# design.net
KiCad netlist of a schematic drawn in Altium Designer
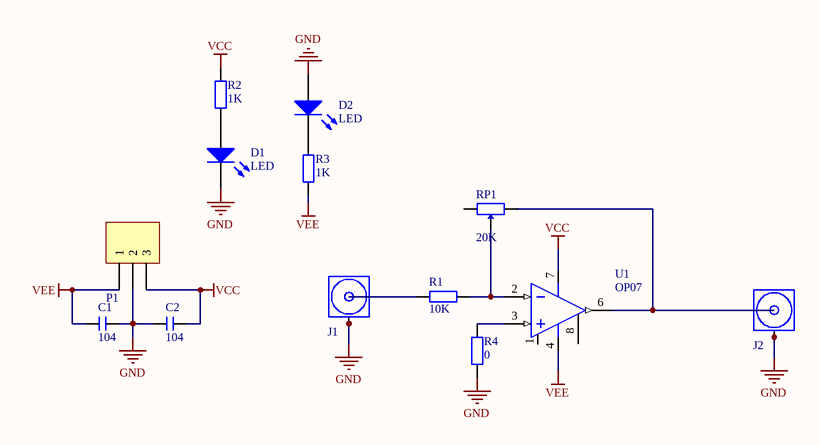
[diagram p0: 反向放大器.SchDoc]

(export (version "E")
  (design (tool "Eeschema 10.0.6"))
  (components
    (comp (ref "C1")
      (value "104")
      (footprint "C 0805")
      (description "无极性贴片电容")
      (fields (field (name "版权归属") "源创客"))
      (libsource (lib "电阻-电容-电感") (part "C"))
    )
    (comp (ref "C2")
      (value "104")
      (footprint "C 0805")
      (description "无极性贴片电容")
      (fields (field (name "版权归属") "源创客"))
      (libsource (lib "电阻-电容-电感") (part "C"))
    )
    (comp (ref "D1")
      (value "LED")
      (footprint "LED_0805")
      (description "发光二极管")
      (fields (field (name "PUBLISHER") "Altium Limited"))
      (libsource (lib "LIB") (part "LED"))
    )
    (comp (ref "D2")
      (value "LED")
      (footprint "LED_0805")
      (description "发光二极管")
      (fields (field (name "PUBLISHER") "Altium Limited"))
      (libsource (lib "LIB") (part "LED"))
    )
    (comp (ref "J1") (value "COAX") (footprint "MCX5.08-5-H") (libsource (lib "LIB") (part "COAX")))
    (comp (ref "J2") (value "COAX") (footprint "MCX5.08-5-H") (libsource (lib "LIB") (part "COAX")))
    (comp (ref "P1")
      (value "Header 3")
      (footprint "HDR3X1_B2")
      (description "接插件")
      (fields (field (name "PUBLISHER") "Altium Limited"))
      (libsource (lib "LIB") (part "Header 3"))
    )
    (comp (ref "R1")
      (value "10K")
      (footprint "R 0805")
      (description "贴片电阻")
      (fields (field (name "版权归属") "源创客"))
      (libsource (lib "电阻-电容-电感") (part "R"))
    )
    (comp (ref "R2")
      (value "1K")
      (footprint "R 0805")
      (description "贴片电阻")
      (fields (field (name "版权归属") "源创客"))
      (libsource (lib "电阻-电容-电感") (part "R"))
    )
    (comp (ref "R3")
      (value "1K")
      (footprint "R 0805")
      (description "贴片电阻")
      (fields (field (name "版权归属") "源创客"))
      (libsource (lib "电阻-电容-电感") (part "R"))
    )
    (comp (ref "R4")
      (value "0")
      (footprint "R 0603")
      (description "贴片电阻")
      (fields (field (name "版权归属") "源创客"))
      (libsource (lib "电阻-电容-电感") (part "R"))
    )
    (comp (ref "RP1")
      (value "20K")
      (footprint "3296W")
      (description "插件单联电位器")
      (fields (field (name "版权归属") "源创客"))
      (libsource (lib "电阻-电容-电感") (part "RP-ID"))
    )
    (comp (ref "U1")
      (value "OP07")
      (footprint "SO8_L")
      (description "Precision Operational Amplifiers")
      (libsource (lib "LIB") (part "OP07"))
    )
  )
  (nets
    (net (code "1") (name "GND") (class "Default")
      (node (ref "C1") (pin "2") (pinfunction "2_2") (pintype "passive"))
      (node (ref "C2") (pin "1") (pinfunction "1_1") (pintype "passive"))
      (node (ref "D1") (pin "2") (pinfunction "K_2") (pintype "passive"))
      (node (ref "D2") (pin "1") (pinfunction "A_1") (pintype "passive"))
      (node (ref "J1") (pin "2") (pinfunction "GND_2") (pintype "passive"))
      (node (ref "J1") (pin "3") (pinfunction "GND_3") (pintype "passive"))
      (node (ref "J1") (pin "4") (pinfunction "GND_4") (pintype "passive"))
      (node (ref "J1") (pin "5") (pinfunction "GND_5") (pintype "passive"))
      (node (ref "J2") (pin "2") (pinfunction "GND_2") (pintype "passive"))
      (node (ref "J2") (pin "3") (pinfunction "GND_3") (pintype "passive"))
      (node (ref "J2") (pin "4") (pinfunction "GND_4") (pintype "passive"))
      (node (ref "J2") (pin "5") (pinfunction "GND_5") (pintype "passive"))
      (node (ref "P1") (pin "2") (pinfunction "2_2") (pintype "passive"))
      (node (ref "R4") (pin "1") (pinfunction "1_1") (pintype "passive"))
    )
    (net (code "2") (name "Net-(D1-A)") (class "Default")
      (node (ref "D1") (pin "1") (pinfunction "A_1") (pintype "passive"))
      (node (ref "R2") (pin "1") (pinfunction "1_1") (pintype "passive"))
    )
    (net (code "3") (name "Net-(D2-K)") (class "Default")
      (node (ref "D2") (pin "2") (pinfunction "K_2") (pintype "passive"))
      (node (ref "R3") (pin "2") (pinfunction "2_2") (pintype "passive"))
    )
    (net (code "4") (name "Net-(J1-Signal)") (class "Default")
      (node (ref "J1") (pin "1") (pinfunction "Signal_1") (pintype "passive"))
      (node (ref "R1") (pin "1") (pinfunction "1_1") (pintype "passive"))
    )
    (net (code "5") (name "Net-(J2-Signal)") (class "Default")
      (node (ref "J2") (pin "1") (pinfunction "Signal_1") (pintype "passive"))
      (node (ref "RP1") (pin "1") (pinfunction "1_1") (pintype "passive"))
      (node (ref "U1") (pin "6") (pinfunction "OUT_6") (pintype "output"))
    )
    (net (code "6") (name "Net-(U1-IN+)") (class "Default")
      (node (ref "R4") (pin "2") (pinfunction "2_2") (pintype "passive"))
      (node (ref "U1") (pin "3") (pinfunction "IN+_3") (pintype "input"))
    )
    (net (code "7") (name "Net-(U1-IN-)") (class "Default")
      (node (ref "R1") (pin "2") (pinfunction "2_2") (pintype "passive"))
      (node (ref "RP1") (pin "2") (pinfunction "2_2") (pintype "passive"))
      (node (ref "U1") (pin "2") (pinfunction "IN-_2") (pintype "input"))
    )
    (net (code "8") (name "VCC") (class "Default")
      (node (ref "C2") (pin "2") (pinfunction "2_2") (pintype "passive"))
      (node (ref "P1") (pin "3") (pinfunction "3_3") (pintype "passive"))
      (node (ref "R2") (pin "2") (pinfunction "2_2") (pintype "passive"))
      (node (ref "U1") (pin "7") (pinfunction "V+_7") (pintype "power_in"))
    )
    (net (code "9") (name "VEE") (class "Default")
      (node (ref "C1") (pin "1") (pinfunction "1_1") (pintype "passive"))
      (node (ref "P1") (pin "1") (pinfunction "1_1") (pintype "passive"))
      (node (ref "R3") (pin "1") (pinfunction "1_1") (pintype "passive"))
      (node (ref "U1") (pin "4") (pinfunction "V-_4") (pintype "power_in"))
    )
    (net (code "10") (name "unconnected-(RP1-Pad3)") (class "Default")
      (node (ref "RP1") (pin "3") (pinfunction "3_3") (pintype "passive"))
    )
    (net (code "11") (name "unconnected-(U1-OFFSET_N1-Pad1)") (class "Default")
      (node (ref "U1") (pin "1") (pinfunction "OFFSET_N1_1") (pintype "passive"))
    )
    (net (code "12") (name "unconnected-(U1-OFFSET_N2-Pad8)") (class "Default")
      (node (ref "U1") (pin "8") (pinfunction "OFFSET_N2_8") (pintype "passive"))
    )
  )
)
